# KSM.net
KiCad netlist of a schematic drawn in EAGLE
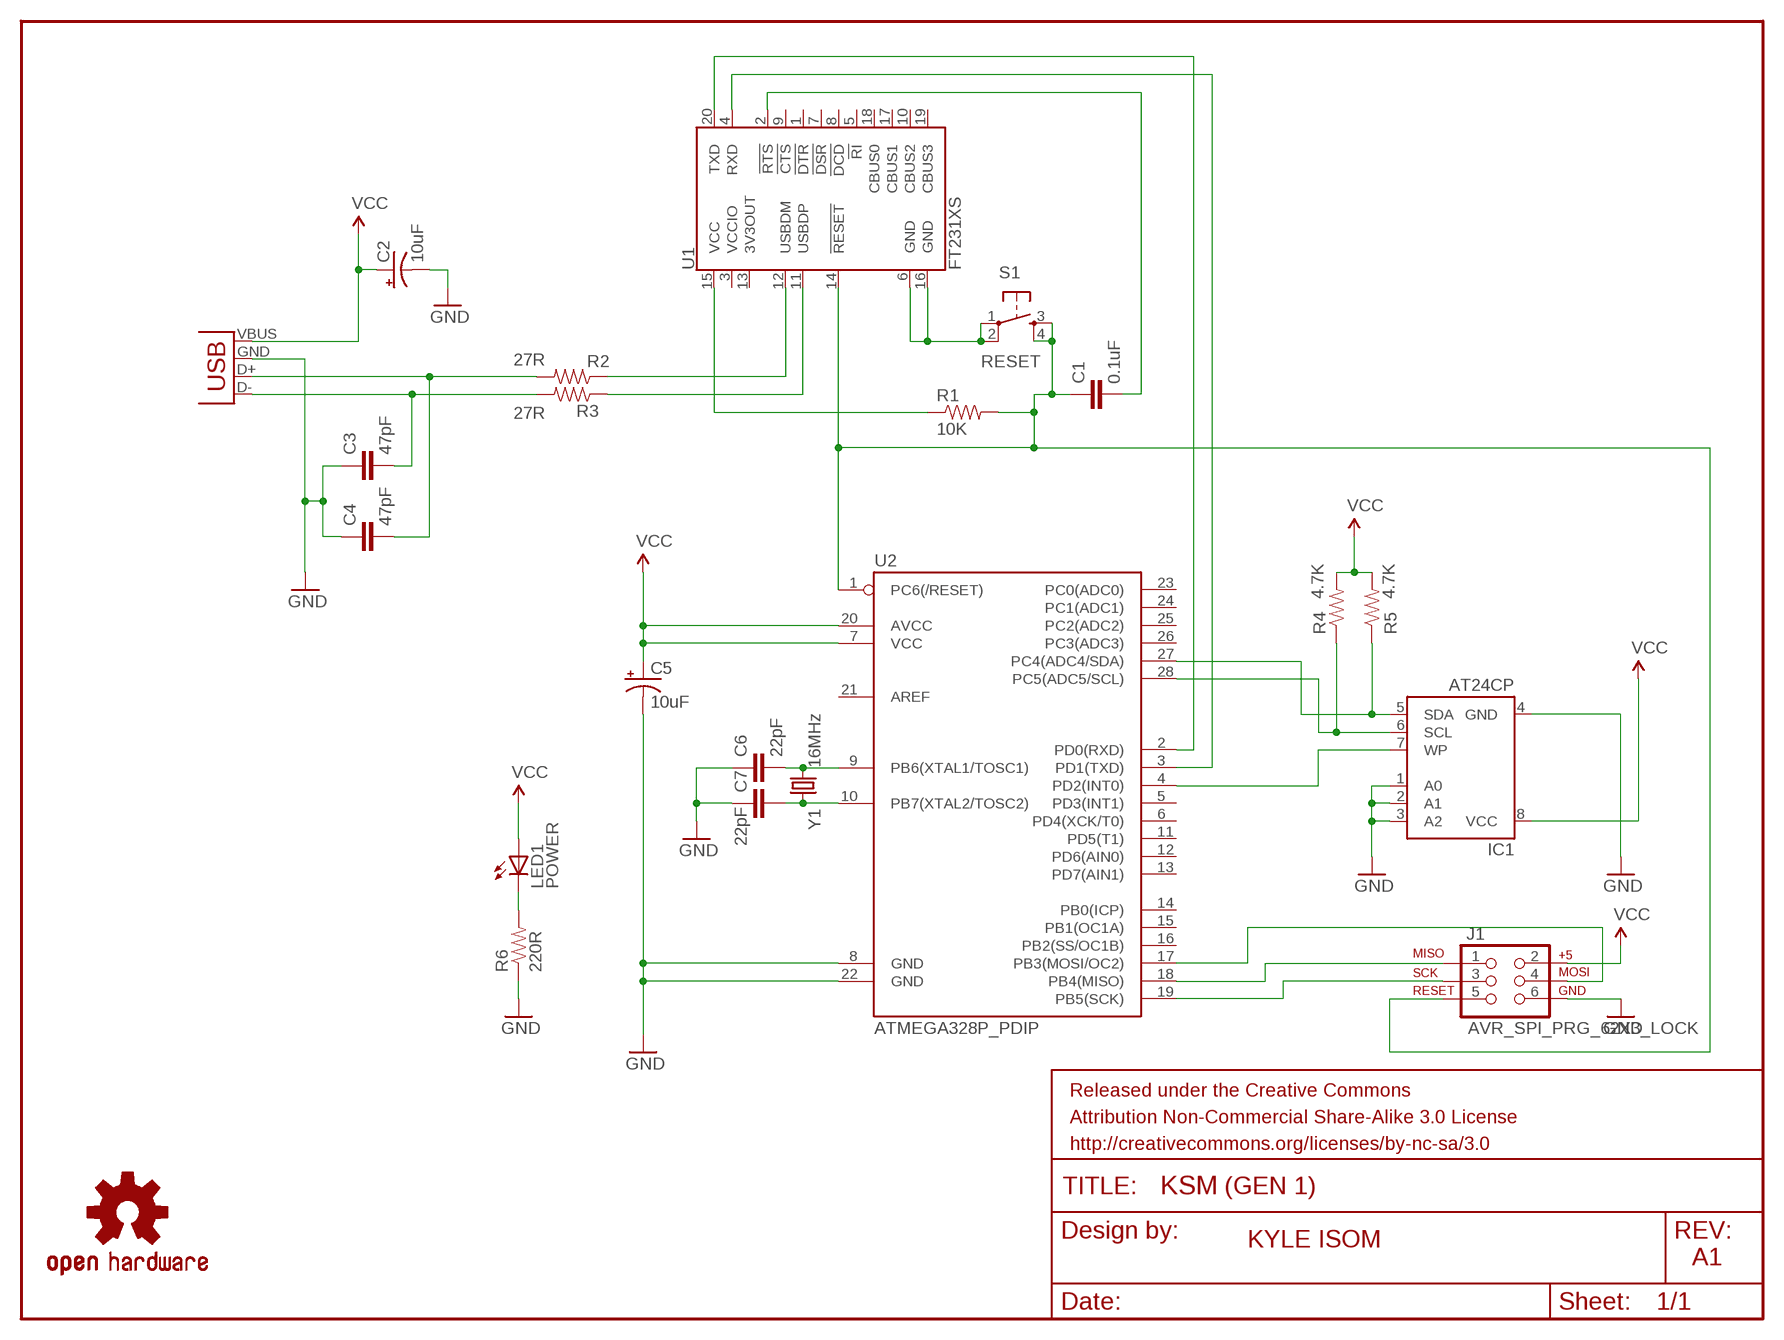
[diagram p0: schematic, sheet 1]

(export (version "E")
  (design (tool "Eeschema 10.0.6"))
  (components
    (comp (ref "C1")
      (value "0.1uF")
      (footprint "eagle-import:CAP-PTH-SMALL")
      (libsource (lib "eagle-import") (part "CAPPTH"))
    )
    (comp (ref "C2")
      (value "10uF")
      (footprint "eagle-import:CPOL-RADIAL-10UF-25V")
      (libsource (lib "eagle-import") (part "CAP_POLPTH2"))
    )
    (comp (ref "C3")
      (value "47pF")
      (footprint "eagle-import:CAP-PTH-SMALL")
      (libsource (lib "eagle-import") (part "CAPPTH"))
    )
    (comp (ref "C4")
      (value "47pF")
      (footprint "eagle-import:CAP-PTH-SMALL")
      (libsource (lib "eagle-import") (part "CAPPTH"))
    )
    (comp (ref "C5")
      (value "10uF")
      (footprint "eagle-import:CPOL-RADIAL-10UF-25V")
      (libsource (lib "eagle-import") (part "CAP_POLPTH2"))
    )
    (comp (ref "C6")
      (value "22pF")
      (footprint "eagle-import:CAP-PTH-SMALL")
      (libsource (lib "eagle-import") (part "CAPPTH"))
    )
    (comp (ref "C7")
      (value "22pF")
      (footprint "eagle-import:CAP-PTH-SMALL")
      (libsource (lib "eagle-import") (part "CAPPTH"))
    )
    (comp (ref "FRAME1")
      (value "FRAME-LETTER")
      (footprint "eagle-import:CREATIVE_COMMONS")
      (libsource (lib "eagle-import") (part "FRAME-LETTER"))
    )
    (comp (ref "IC1")
      (value "AT24CP")
      (footprint "eagle-import:DIL08")
      (fields (field (name "MPN") "AT24C1024BW-SH-B"))
      (libsource (lib "eagle-import") (part "AT24CP"))
    )
    (comp (ref "J1")
      (value "AVR_SPI_PRG_62X3_LOCK")
      (footprint "eagle-import:2X3_LOCK")
      (libsource (lib "eagle-import") (part "AVR_SPI_PRG_62X3_LOCK"))
    )
    (comp (ref "JP1")
      (value "USB-A-H")
      (footprint "eagle-import:USB-A-H")
      (libsource (lib "eagle-import") (part "USB-A-H"))
    )
    (comp (ref "LED1")
      (value "POWER")
      (footprint "eagle-import:LED3MM")
      (libsource (lib "eagle-import") (part "LED3MM"))
    )
    (comp (ref "LOGO1")
      (value "OSHW-LOGOL")
      (footprint "eagle-import:OSHW-LOGO-L")
      (libsource (lib "eagle-import") (part "OSHW-LOGOL"))
    )
    (comp (ref "R1")
      (value "10K")
      (footprint "eagle-import:AXIAL-0.4")
      (libsource (lib "eagle-import") (part "RESISTORPTH-1/4W"))
    )
    (comp (ref "R2")
      (value "27R")
      (footprint "eagle-import:AXIAL-0.4")
      (libsource (lib "eagle-import") (part "RESISTORPTH-1/4W"))
    )
    (comp (ref "R3")
      (value "27R")
      (footprint "eagle-import:AXIAL-0.4")
      (libsource (lib "eagle-import") (part "RESISTORPTH-1/4W"))
    )
    (comp (ref "R4")
      (value "4.7K")
      (footprint "eagle-import:AXIAL-0.4")
      (libsource (lib "eagle-import") (part "RESISTORPTH-1/4W"))
    )
    (comp (ref "R5")
      (value "4.7K")
      (footprint "eagle-import:AXIAL-0.4")
      (libsource (lib "eagle-import") (part "RESISTORPTH-1/4W"))
    )
    (comp (ref "R6")
      (value "220R")
      (footprint "eagle-import:AXIAL-0.4")
      (libsource (lib "eagle-import") (part "RESISTORPTH-1/4W"))
    )
    (comp (ref "S1")
      (value "RESET")
      (footprint "eagle-import:TACTILE-PTH")
      (libsource (lib "eagle-import") (part "TAC_SWITCHPTH"))
    )
    (comp (ref "U1")
      (value "FT231XS")
      (footprint "eagle-import:SSOP20_L")
      (libsource (lib "eagle-import") (part "FT231XS"))
    )
    (comp (ref "U2")
      (value "ATMEGA328P_PDIP")
      (footprint "eagle-import:DIL28-3")
      (libsource (lib "eagle-import") (part "ATMEGA328P_PDIP"))
    )
    (comp (ref "Y1")
      (value "16MHz")
      (footprint "eagle-import:HC49US")
      (libsource (lib "eagle-import") (part "CRYSTALHC49US"))
    )
  )
  (nets
    (net (code "1") (name "GND") (class "Default")
      (node (ref "C2") (pin "2") (pinfunction "-_2") (pintype "passive"))
      (node (ref "C3") (pin "1") (pinfunction "1_1") (pintype "passive"))
      (node (ref "C4") (pin "1") (pinfunction "1_1") (pintype "passive"))
      (node (ref "C5") (pin "2") (pinfunction "-_2") (pintype "passive"))
      (node (ref "C6") (pin "1") (pinfunction "1_1") (pintype "passive"))
      (node (ref "C7") (pin "1") (pinfunction "1_1") (pintype "passive"))
      (node (ref "IC1") (pin "1") (pinfunction "A0_1") (pintype "input"))
      (node (ref "IC1") (pin "2") (pinfunction "A1_2") (pintype "input"))
      (node (ref "IC1") (pin "3") (pinfunction "A2_3") (pintype "input"))
      (node (ref "IC1") (pin "4") (pinfunction "GND_4") (pintype "power_in"))
      (node (ref "J1") (pin "6") (pinfunction "6_6") (pintype "passive"))
      (node (ref "JP1") (pin "GND") (pinfunction "VBUS_GND") (pintype "bidirectional"))
      (node (ref "R6") (pin "P$1") (pinfunction "1_P$1") (pintype "passive"))
      (node (ref "U2") (pin "22") (pinfunction "GND_22") (pintype "bidirectional"))
      (node (ref "U2") (pin "8") (pinfunction "GND_8") (pintype "bidirectional"))
    )
    (net (code "2") (name "Net-(IC1-SCL)") (class "Default")
      (node (ref "IC1") (pin "6") (pinfunction "SCL_6") (pintype "bidirectional"))
      (node (ref "R4") (pin "P$1") (pinfunction "1_P$1") (pintype "passive"))
      (node (ref "U2") (pin "28") (pinfunction "PC5(ADC5/SCL)_28") (pintype "bidirectional"))
    )
    (net (code "3") (name "Net-(IC1-SDA)") (class "Default")
      (node (ref "IC1") (pin "5") (pinfunction "SDA_5") (pintype "bidirectional"))
      (node (ref "R5") (pin "P$1") (pinfunction "1_P$1") (pintype "passive"))
      (node (ref "U2") (pin "27") (pinfunction "PC4(ADC4/SDA)_27") (pintype "bidirectional"))
    )
    (net (code "4") (name "Net-(IC1-WP)") (class "Default")
      (node (ref "IC1") (pin "7") (pinfunction "WP_7") (pintype "input"))
      (node (ref "U2") (pin "4") (pinfunction "PD2(INT0)_4") (pintype "bidirectional"))
    )
    (net (code "5") (name "Net-(JP1-D+)") (class "Default")
      (node (ref "C3") (pin "2") (pinfunction "2_2") (pintype "passive"))
      (node (ref "JP1") (pin "D-") (pinfunction "D+_D-") (pintype "bidirectional"))
      (node (ref "R3") (pin "P$2") (pinfunction "2_P$2") (pintype "passive"))
    )
    (net (code "6") (name "Net-(JP1-D-)") (class "Default")
      (node (ref "C4") (pin "2") (pinfunction "2_2") (pintype "passive"))
      (node (ref "JP1") (pin "D+") (pinfunction "D-_D+") (pintype "bidirectional"))
      (node (ref "R2") (pin "P$2") (pinfunction "2_P$2") (pintype "passive"))
    )
    (net (code "7") (name "Net-(LED1-C)") (class "Default")
      (node (ref "LED1") (pin "K") (pinfunction "C_K") (pintype "passive"))
      (node (ref "R6") (pin "P$2") (pinfunction "2_P$2") (pintype "passive"))
    )
    (net (code "8") (name "Net-(R1-1)") (class "Default")
      (node (ref "R1") (pin "P$1") (pinfunction "1_P$1") (pintype "passive"))
      (node (ref "U1") (pin "15") (pinfunction "VCC_15") (pintype "bidirectional"))
    )
    (net (code "9") (name "Net-(R1-2)") (class "Default")
      (node (ref "C1") (pin "1") (pinfunction "1_1") (pintype "passive"))
      (node (ref "J1") (pin "5") (pinfunction "5_5") (pintype "passive"))
      (node (ref "R1") (pin "P$2") (pinfunction "2_P$2") (pintype "passive"))
      (node (ref "S1") (pin "3") (pinfunction "3_3") (pintype "passive"))
      (node (ref "S1") (pin "4") (pinfunction "4_4") (pintype "passive"))
      (node (ref "U1") (pin "14") (pinfunction "~{RESET}_14") (pintype "bidirectional"))
      (node (ref "U2") (pin "1") (pinfunction "PC6(/RESET)_1") (pintype "bidirectional"))
    )
    (net (code "10") (name "Net-(R2-1)") (class "Default")
      (node (ref "R2") (pin "P$1") (pinfunction "1_P$1") (pintype "passive"))
      (node (ref "U1") (pin "12") (pinfunction "USBDM_12") (pintype "bidirectional"))
    )
    (net (code "11") (name "Net-(R3-1)") (class "Default")
      (node (ref "R3") (pin "P$1") (pinfunction "1_P$1") (pintype "passive"))
      (node (ref "U1") (pin "11") (pinfunction "USBDP_11") (pintype "bidirectional"))
    )
    (net (code "12") (name "Net-(S1-Pad1)") (class "Default")
      (node (ref "S1") (pin "1") (pinfunction "1_1") (pintype "passive"))
      (node (ref "S1") (pin "2") (pinfunction "2_2") (pintype "passive"))
      (node (ref "U1") (pin "16") (pinfunction "GND_16") (pintype "bidirectional"))
      (node (ref "U1") (pin "6") (pinfunction "GND_6") (pintype "bidirectional"))
    )
    (net (code "13") (name "Net-(U1-RXD)") (class "Default")
      (node (ref "U1") (pin "4") (pinfunction "RXD_4") (pintype "bidirectional"))
      (node (ref "U2") (pin "3") (pinfunction "PD1(TXD)_3") (pintype "bidirectional"))
    )
    (net (code "14") (name "Net-(U1-TXD)") (class "Default")
      (node (ref "U1") (pin "20") (pinfunction "TXD_20") (pintype "bidirectional"))
      (node (ref "U2") (pin "2") (pinfunction "PD0(RXD)_2") (pintype "bidirectional"))
    )
    (net (code "15") (name "Net-(U1-~{RTS})") (class "Default")
      (node (ref "C1") (pin "2") (pinfunction "2_2") (pintype "passive"))
      (node (ref "U1") (pin "2") (pinfunction "~{RTS}_2") (pintype "bidirectional"))
    )
    (net (code "16") (name "Net-(U2-PB3(MOSI{slash}OC2))") (class "Default")
      (node (ref "J1") (pin "4") (pinfunction "4_4") (pintype "passive"))
      (node (ref "U2") (pin "17") (pinfunction "PB3(MOSI/OC2)_17") (pintype "bidirectional"))
    )
    (net (code "17") (name "Net-(U2-PB4(MISO))") (class "Default")
      (node (ref "J1") (pin "1") (pinfunction "1_1") (pintype "passive"))
      (node (ref "U2") (pin "18") (pinfunction "PB4(MISO)_18") (pintype "bidirectional"))
    )
    (net (code "18") (name "Net-(U2-PB5(SCK))") (class "Default")
      (node (ref "J1") (pin "3") (pinfunction "3_3") (pintype "passive"))
      (node (ref "U2") (pin "19") (pinfunction "PB5(SCK)_19") (pintype "bidirectional"))
    )
    (net (code "19") (name "Net-(U2-PB6(XTAL1{slash}TOSC1))") (class "Default")
      (node (ref "C6") (pin "2") (pinfunction "2_2") (pintype "passive"))
      (node (ref "U2") (pin "9") (pinfunction "PB6(XTAL1/TOSC1)_9") (pintype "bidirectional"))
      (node (ref "Y1") (pin "2") (pinfunction "2_2") (pintype "passive"))
    )
    (net (code "20") (name "Net-(U2-PB7(XTAL2{slash}TOSC2))") (class "Default")
      (node (ref "C7") (pin "2") (pinfunction "2_2") (pintype "passive"))
      (node (ref "U2") (pin "10") (pinfunction "PB7(XTAL2/TOSC2)_10") (pintype "bidirectional"))
      (node (ref "Y1") (pin "1") (pinfunction "1_1") (pintype "passive"))
    )
    (net (code "21") (name "VCC") (class "Default")
      (node (ref "C2") (pin "1") (pinfunction "+_1") (pintype "passive"))
      (node (ref "C5") (pin "1") (pinfunction "+_1") (pintype "passive"))
      (node (ref "IC1") (pin "8") (pinfunction "VCC_8") (pintype "power_in"))
      (node (ref "J1") (pin "2") (pinfunction "2_2") (pintype "passive"))
      (node (ref "JP1") (pin "VBUS") (pinfunction "GND_VBUS") (pintype "bidirectional"))
      (node (ref "LED1") (pin "A") (pinfunction "A_A") (pintype "passive"))
      (node (ref "R4") (pin "P$2") (pinfunction "2_P$2") (pintype "passive"))
      (node (ref "R5") (pin "P$2") (pinfunction "2_P$2") (pintype "passive"))
      (node (ref "U2") (pin "20") (pinfunction "AVCC_20") (pintype "bidirectional"))
      (node (ref "U2") (pin "7") (pinfunction "VCC_7") (pintype "bidirectional"))
    )
    (net (code "22") (name "unconnected-(U1-3V3OUT-Pad13)") (class "Default")
      (node (ref "U1") (pin "13") (pinfunction "3V3OUT_13") (pintype "bidirectional"))
    )
    (net (code "23") (name "unconnected-(U1-CBUS0-Pad18)") (class "Default")
      (node (ref "U1") (pin "18") (pinfunction "CBUS0_18") (pintype "bidirectional"))
    )
    (net (code "24") (name "unconnected-(U1-CBUS1-Pad17)") (class "Default")
      (node (ref "U1") (pin "17") (pinfunction "CBUS1_17") (pintype "bidirectional"))
    )
    (net (code "25") (name "unconnected-(U1-CBUS2-Pad10)") (class "Default")
      (node (ref "U1") (pin "10") (pinfunction "CBUS2_10") (pintype "bidirectional"))
    )
    (net (code "26") (name "unconnected-(U1-CBUS3-Pad19)") (class "Default")
      (node (ref "U1") (pin "19") (pinfunction "CBUS3_19") (pintype "bidirectional"))
    )
    (net (code "27") (name "unconnected-(U1-VCCIO-Pad3)") (class "Default")
      (node (ref "U1") (pin "3") (pinfunction "VCCIO_3") (pintype "bidirectional"))
    )
    (net (code "28") (name "unconnected-(U1-~{CTS}-Pad9)") (class "Default")
      (node (ref "U1") (pin "9") (pinfunction "~{CTS}_9") (pintype "bidirectional"))
    )
    (net (code "29") (name "unconnected-(U1-~{DCD}-Pad8)") (class "Default")
      (node (ref "U1") (pin "8") (pinfunction "~{DCD}_8") (pintype "bidirectional"))
    )
    (net (code "30") (name "unconnected-(U1-~{DSR}-Pad7)") (class "Default")
      (node (ref "U1") (pin "7") (pinfunction "~{DSR}_7") (pintype "bidirectional"))
    )
    (net (code "31") (name "unconnected-(U1-~{DTR}-Pad1)") (class "Default")
      (node (ref "U1") (pin "1") (pinfunction "~{DTR}_1") (pintype "bidirectional"))
    )
    (net (code "32") (name "unconnected-(U1-~{RI}-Pad5)") (class "Default")
      (node (ref "U1") (pin "5") (pinfunction "~{RI}_5") (pintype "bidirectional"))
    )
    (net (code "33") (name "unconnected-(U2-AREF-Pad21)") (class "Default")
      (node (ref "U2") (pin "21") (pinfunction "AREF_21") (pintype "bidirectional"))
    )
    (net (code "34") (name "unconnected-(U2-PB0(ICP)-Pad14)") (class "Default")
      (node (ref "U2") (pin "14") (pinfunction "PB0(ICP)_14") (pintype "bidirectional"))
    )
    (net (code "35") (name "unconnected-(U2-PB1(OC1A)-Pad15)") (class "Default")
      (node (ref "U2") (pin "15") (pinfunction "PB1(OC1A)_15") (pintype "bidirectional"))
    )
    (net (code "36") (name "unconnected-(U2-PB2(SS{slash}OC1B)-Pad16)") (class "Default")
      (node (ref "U2") (pin "16") (pinfunction "PB2(SS/OC1B)_16") (pintype "bidirectional"))
    )
    (net (code "37") (name "unconnected-(U2-PC0(ADC0)-Pad23)") (class "Default")
      (node (ref "U2") (pin "23") (pinfunction "PC0(ADC0)_23") (pintype "bidirectional"))
    )
    (net (code "38") (name "unconnected-(U2-PC1(ADC1)-Pad24)") (class "Default")
      (node (ref "U2") (pin "24") (pinfunction "PC1(ADC1)_24") (pintype "bidirectional"))
    )
    (net (code "39") (name "unconnected-(U2-PC2(ADC2)-Pad25)") (class "Default")
      (node (ref "U2") (pin "25") (pinfunction "PC2(ADC2)_25") (pintype "bidirectional"))
    )
    (net (code "40") (name "unconnected-(U2-PC3(ADC3)-Pad26)") (class "Default")
      (node (ref "U2") (pin "26") (pinfunction "PC3(ADC3)_26") (pintype "bidirectional"))
    )
    (net (code "41") (name "unconnected-(U2-PD3(INT1)-Pad5)") (class "Default")
      (node (ref "U2") (pin "5") (pinfunction "PD3(INT1)_5") (pintype "bidirectional"))
    )
    (net (code "42") (name "unconnected-(U2-PD4(XCK{slash}T0)-Pad6)") (class "Default")
      (node (ref "U2") (pin "6") (pinfunction "PD4(XCK/T0)_6") (pintype "bidirectional"))
    )
    (net (code "43") (name "unconnected-(U2-PD5(T1)-Pad11)") (class "Default")
      (node (ref "U2") (pin "11") (pinfunction "PD5(T1)_11") (pintype "bidirectional"))
    )
    (net (code "44") (name "unconnected-(U2-PD6(AIN0)-Pad12)") (class "Default")
      (node (ref "U2") (pin "12") (pinfunction "PD6(AIN0)_12") (pintype "bidirectional"))
    )
    (net (code "45") (name "unconnected-(U2-PD7(AIN1)-Pad13)") (class "Default")
      (node (ref "U2") (pin "13") (pinfunction "PD7(AIN1)_13") (pintype "bidirectional"))
    )
  )
)
